# Sensors.net
KiCad netlist of a schematic drawn in Altium Designer
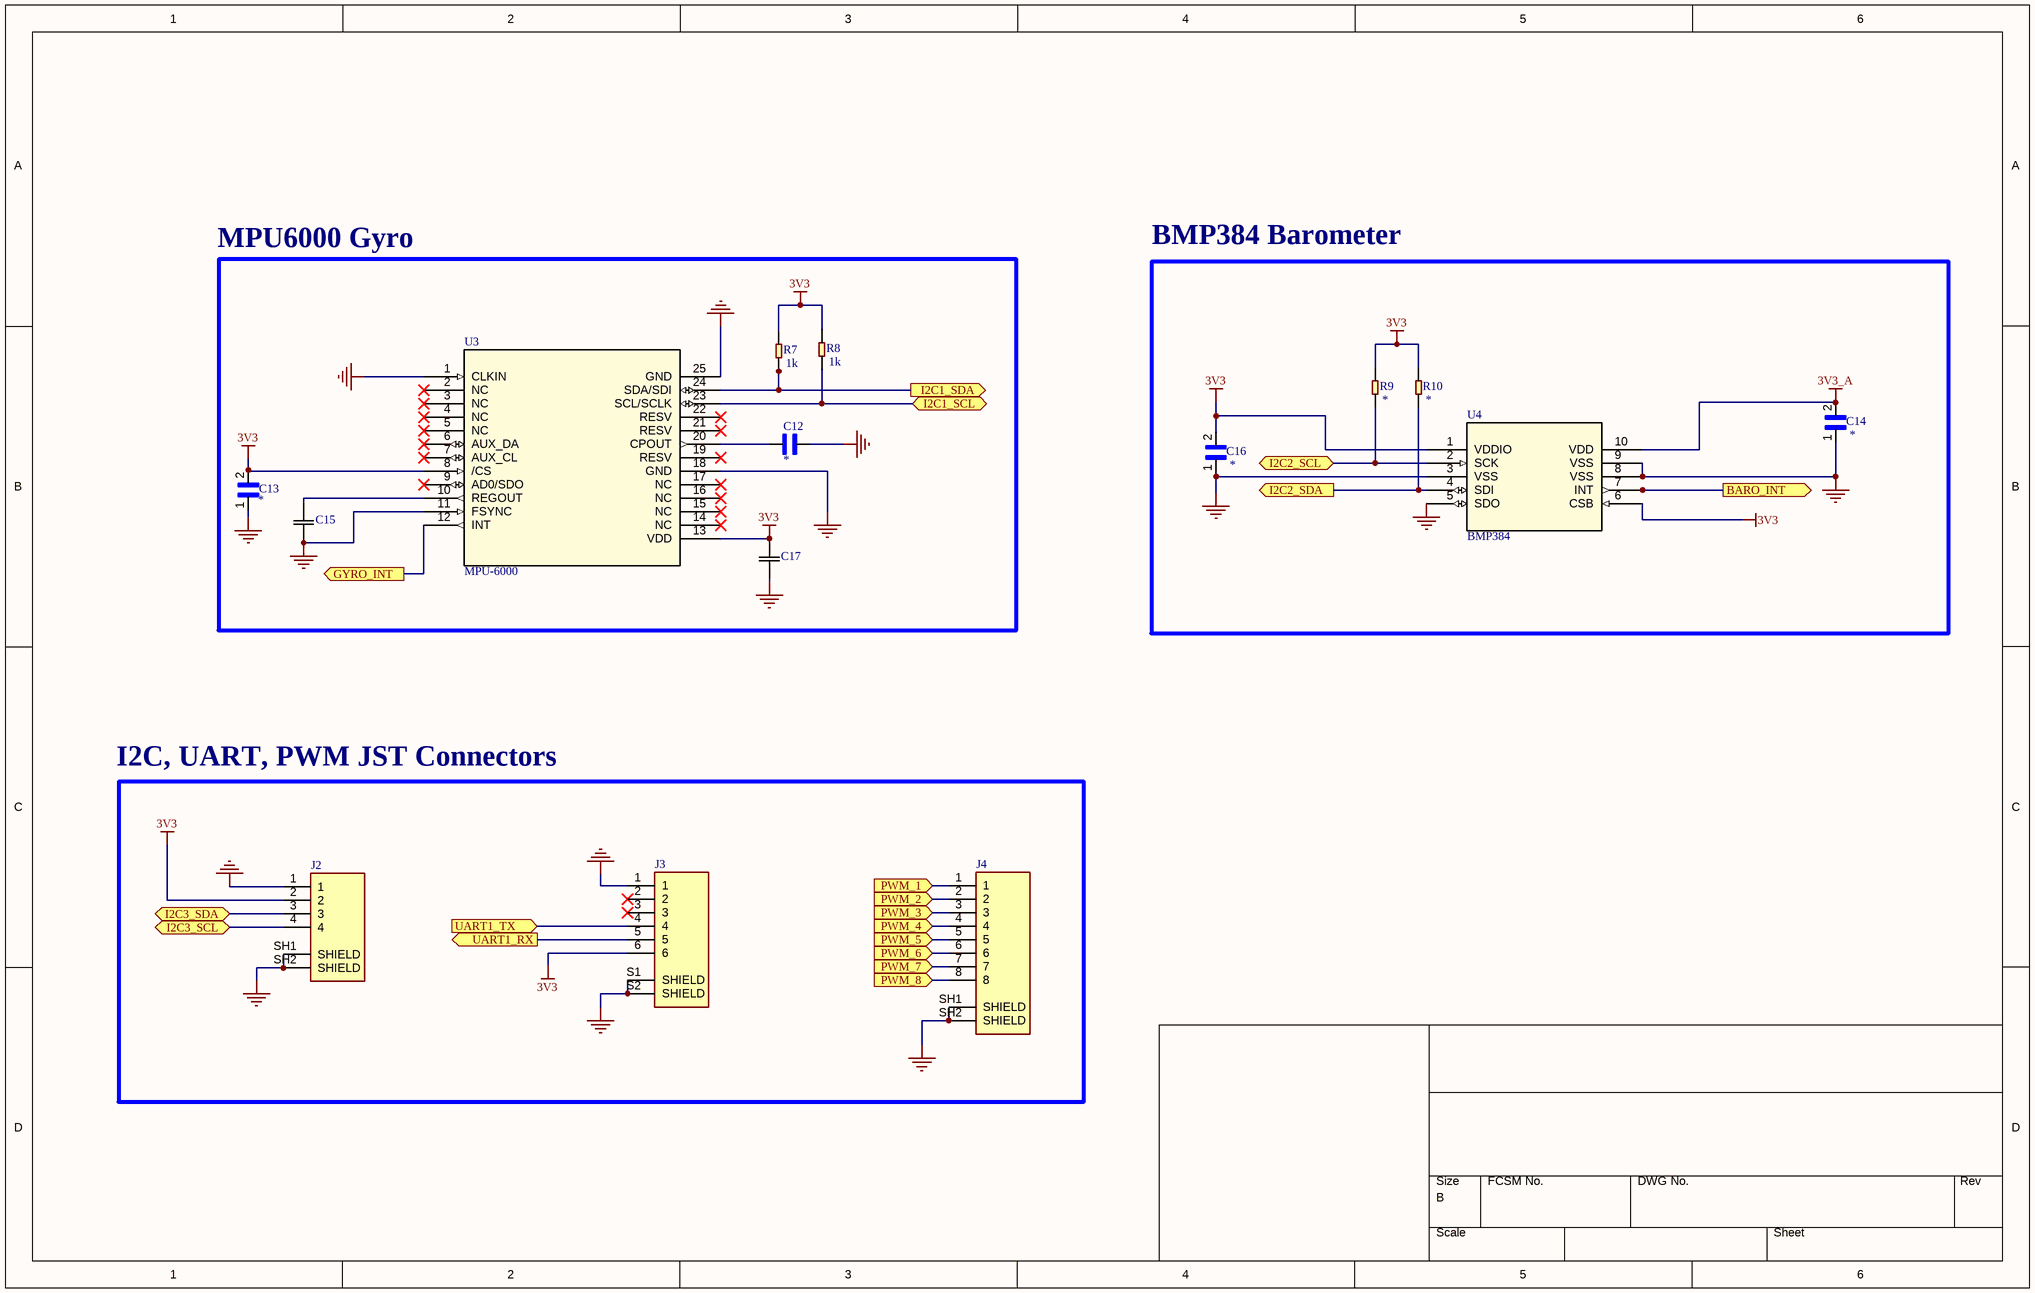
[diagram p0: Sensors.SchDoc]

(export (version "E")
  (design (tool "Eeschema 10.0.6"))
  (components
    (comp (ref "C12")
      (value "GRM155R70J222KA01D")
      (footprint "CAPC1005X55N")
      (description "Cap Ceramic 0.0022uF 6.3V X7R 10% SMD 0402 125Â°C Paper T/R")
      (fields (field (name "ALTIUM_VALUE") "*"))
      (libsource (lib "GRM155R70J222KA01D") (part "GRM155R70J222KA01D"))
    )
    (comp (ref "C13")
      (value "GRM033R71A103KA01D")
      (footprint "CAPC0603X33N")
      (description "SMD Capacitor X7R(EIA) with Capacitance: 10000pF Tol. 10%. Rated Voltage: 10Vdc")
      (fields (field (name "ALTIUM_VALUE") "*") (field (name "MF") "Murata"))
      (libsource (lib "GRM033R71A103KA01D") (part "GRM033R71A103KA01D"))
    )
    (comp (ref "C14")
      (value "GRM033R61A104KE15D")
      (footprint "CAPC0603X33N")
      (description "SMD capacitor X5R(EIA) with capacitance 0.10uF Tol.10%. Rated voltage 10Vdc 85C")
      (fields (field (name "MF") "Murata Electronics") (field (name "ALTIUM_VALUE") "*"))
      (libsource (lib "GRM033R61A104KE15D") (part "GRM033R61A104KE15D"))
    )
    (comp (ref "C15")
      (value "CC0201MRX5R6BB105")
      (footprint "CAP_CC0201_YAG")
      (description "No Description Available")
      (libsource (lib "CC0201MRX5R6BB105") (part "CC0201MRX5R6BB105"))
    )
    (comp (ref "C16")
      (value "GRM033R61A104KE15D")
      (footprint "CAPC0603X33N")
      (description "SMD capacitor X5R(EIA) with capacitance 0.10uF Tol.10%. Rated voltage 10Vdc 85C")
      (fields (field (name "MF") "Murata Electronics") (field (name "ALTIUM_VALUE") "*"))
      (libsource (lib "GRM033R61A104KE15D") (part "GRM033R61A104KE15D"))
    )
    (comp (ref "C17")
      (value "CC0201MRX5R6BB105")
      (footprint "CAP_CC0201_YAG")
      (description "No Description Available")
      (libsource (lib "CC0201MRX5R6BB105") (part "CC0201MRX5R6BB105"))
    )
    (comp (ref "J2")
      (value "SM04B-GHS-TB(LF)(SN)-")
      (footprint "JST_SM04B-GHS-TB(LF)(SN)-")
      (description "Connector Header Surface Mount, Right Angle 4 position 0.049 _1.25mm_")
      (fields (field (name "MP") "SM04B-GHS-TB_LF__SN_-") (field (name "MF") "JST Sales"))
      (libsource (lib "SM04B-GHS-TB_LF__SN_-") (part "SM04B-GHS-TB(LF)(SN)-"))
    )
    (comp (ref "J3")
      (value "SM06B-GHS-TB(LF)(SN)")
      (footprint "JST_SM06B-GHS-TB(LF)(SN)")
      (fields (field (name "MP") "SM06B-GHS-TB_LF__SN_") (field (name "MF") "JST Sales"))
      (libsource (lib "SM06B-GHS-TB_LF__SN_") (part "SM06B-GHS-TB(LF)(SN)"))
    )
    (comp (ref "J4")
      (value "SM08B-GHS-TB(LF)(SN)")
      (footprint "JST_SM08B-GHS-TB(LF)(SN)")
      (description "Connector Header Surface Mount, Right Angle 8 position 0.049 _1.25mm_")
      (fields (field (name "MF") "JST Sales") (field (name "DIGI-KEY_PART_NUMBER") "455-1570-1-ND"))
      (libsource (lib "SM08B-GHS-TB_LF__SN_") (part "SM08B-GHS-TB(LF)(SN)"))
    )
    (comp (ref "R7")
      (value "1k")
      (footprint "R0402")
      (description "1 kOhms Â±5% 0.063W, 1/16W Chip Resistor 0402 (1005 Metric) Moisture Resistant Thick Film")
      (fields (field (name "MP") "RC0402JR-071KL") (field (name "DIGI-KEY_PART_NUMBER") "311-1.0KJRTR-ND"))
      (libsource (lib "SMD-RES-1K-5_-1_16W_0402_") (part "SMD-RES-1K-5%-1/16W(0402)"))
    )
    (comp (ref "R8")
      (value "1k")
      (footprint "R0402")
      (description "1 kOhms Â±5% 0.063W, 1/16W Chip Resistor 0402 (1005 Metric) Moisture Resistant Thick Film")
      (fields (field (name "MP") "RC0402JR-071KL") (field (name "DIGI-KEY_PART_NUMBER") "311-1.0KJRTR-ND"))
      (libsource (lib "SMD-RES-1K-5_-1_16W_0402_") (part "SMD-RES-1K-5%-1/16W(0402)"))
    )
    (comp (ref "R9")
      (value "SMD-RES-1K-5%-1/16W(0402)")
      (footprint "R0402")
      (description "1 kOhms Â±5% 0.063W, 1/16W Chip Resistor 0402 (1005 Metric) Moisture Resistant Thick Film")
      (fields
        (field (name "ALTIUM_VALUE") "*")
        (field (name "MP") "RC0402JR-071KL")
        (field (name "DIGI-KEY_PART_NUMBER") "311-1.0KJRTR-ND")
      )
      (libsource (lib "SMD-RES-1K-5_-1_16W_0402_") (part "SMD-RES-1K-5%-1/16W(0402)"))
    )
    (comp (ref "R10")
      (value "SMD-RES-1K-5%-1/16W(0402)")
      (footprint "R0402")
      (description "1 kOhms Â±5% 0.063W, 1/16W Chip Resistor 0402 (1005 Metric) Moisture Resistant Thick Film")
      (fields
        (field (name "ALTIUM_VALUE") "*")
        (field (name "MP") "RC0402JR-071KL")
        (field (name "DIGI-KEY_PART_NUMBER") "311-1.0KJRTR-ND")
      )
      (libsource (lib "SMD-RES-1K-5_-1_16W_0402_") (part "SMD-RES-1K-5%-1/16W(0402)"))
    )
    (comp (ref "U3")
      (value "MPU-6000")
      (footprint "QFN24_4X4X0P9_IVS")
      (description "No Description Available")
      (libsource (lib "MPU-6000") (part "MPU-6000"))
    )
    (comp (ref "U4")
      (value "BMP384")
      (footprint "LGA10_2.0X2.0X0.95_BOS")
      (description "No Description Available")
      (libsource (lib "BMP384") (part "BMP384"))
    )
  )
  (nets
    (net (code "1") (name "/BARO_INT") (class "Default")
      (node (ref "U4") (pin "7") (pinfunction "INT_7") (pintype "output"))
    )
    (net (code "2") (name "/GYRO_INT") (class "Default")
      (node (ref "U3") (pin "12") (pinfunction "INT_12") (pintype "output"))
    )
    (net (code "3") (name "/I2C1_SCL") (class "Default")
      (node (ref "R8") (pin "1") (pinfunction "1_1") (pintype "passive"))
      (node (ref "U3") (pin "23") (pinfunction "SCL/SCLK_23") (pintype "bidirectional"))
    )
    (net (code "4") (name "/I2C1_SDA") (class "Default")
      (node (ref "R7") (pin "1") (pinfunction "1_1") (pintype "passive"))
      (node (ref "U3") (pin "24") (pinfunction "SDA/SDI_24") (pintype "bidirectional"))
    )
    (net (code "5") (name "/I2C2_SCL") (class "Default")
      (node (ref "R9") (pin "1") (pinfunction "1_1") (pintype "passive"))
      (node (ref "U4") (pin "2") (pinfunction "SCK_2") (pintype "input"))
    )
    (net (code "6") (name "/I2C2_SDA") (class "Default")
      (node (ref "R10") (pin "1") (pinfunction "1_1") (pintype "passive"))
      (node (ref "U4") (pin "4") (pinfunction "SDI_4") (pintype "bidirectional"))
    )
    (net (code "7") (name "/I2C3_SCL") (class "Default")
      (node (ref "J2") (pin "4") (pinfunction "4_4") (pintype "passive"))
    )
    (net (code "8") (name "/I2C3_SDA") (class "Default")
      (node (ref "J2") (pin "3") (pinfunction "3_3") (pintype "passive"))
    )
    (net (code "9") (name "/PWM_1") (class "Default")
      (node (ref "J4") (pin "1") (pinfunction "1_1") (pintype "passive"))
    )
    (net (code "10") (name "/PWM_2") (class "Default")
      (node (ref "J4") (pin "2") (pinfunction "2_2") (pintype "passive"))
    )
    (net (code "11") (name "/PWM_3") (class "Default")
      (node (ref "J4") (pin "3") (pinfunction "3_3") (pintype "passive"))
    )
    (net (code "12") (name "/PWM_4") (class "Default")
      (node (ref "J4") (pin "4") (pinfunction "4_4") (pintype "passive"))
    )
    (net (code "13") (name "/PWM_5") (class "Default")
      (node (ref "J4") (pin "5") (pinfunction "5_5") (pintype "passive"))
    )
    (net (code "14") (name "/PWM_6") (class "Default")
      (node (ref "J4") (pin "6") (pinfunction "6_6") (pintype "passive"))
    )
    (net (code "15") (name "/PWM_7") (class "Default")
      (node (ref "J4") (pin "7") (pinfunction "7_7") (pintype "passive"))
    )
    (net (code "16") (name "/PWM_8") (class "Default")
      (node (ref "J4") (pin "8") (pinfunction "8_8") (pintype "passive"))
    )
    (net (code "17") (name "/UART1_RX") (class "Default")
      (node (ref "J3") (pin "5") (pinfunction "5_5") (pintype "passive"))
    )
    (net (code "18") (name "/UART1_TX") (class "Default")
      (node (ref "J3") (pin "4") (pinfunction "4_4") (pintype "passive"))
    )
    (net (code "19") (name "3V3") (class "Default")
      (node (ref "C13") (pin "2") (pinfunction "2_2") (pintype "passive"))
      (node (ref "C16") (pin "2") (pinfunction "2_2") (pintype "passive"))
      (node (ref "C17") (pin "2") (pinfunction "2_2") (pintype "passive"))
      (node (ref "J2") (pin "2") (pinfunction "2_2") (pintype "passive"))
      (node (ref "J3") (pin "6") (pinfunction "6_6") (pintype "passive"))
      (node (ref "R10") (pin "2") (pinfunction "2_2") (pintype "passive"))
      (node (ref "R7") (pin "2") (pinfunction "2_2") (pintype "passive"))
      (node (ref "R8") (pin "2") (pinfunction "2_2") (pintype "passive"))
      (node (ref "R9") (pin "2") (pinfunction "2_2") (pintype "passive"))
      (node (ref "U3") (pin "13") (pinfunction "VDD_13") (pintype "power_in"))
      (node (ref "U3") (pin "8") (pinfunction "/CS_8") (pintype "input"))
      (node (ref "U4") (pin "1") (pinfunction "VDDIO_1") (pintype "power_in"))
      (node (ref "U4") (pin "6") (pinfunction "CSB_6") (pintype "input"))
    )
    (net (code "20") (name "3V3_A") (class "Default")
      (node (ref "C14") (pin "2") (pinfunction "2_2") (pintype "passive"))
      (node (ref "U4") (pin "10") (pinfunction "VDD_10") (pintype "power_in"))
    )
    (net (code "21") (name "GND") (class "Default")
      (node (ref "C12") (pin "1") (pinfunction "1_1") (pintype "passive"))
      (node (ref "C13") (pin "1") (pinfunction "1_1") (pintype "passive"))
      (node (ref "C14") (pin "1") (pinfunction "1_1") (pintype "passive"))
      (node (ref "C15") (pin "1") (pinfunction "1_1") (pintype "passive"))
      (node (ref "C16") (pin "1") (pinfunction "1_1") (pintype "passive"))
      (node (ref "C17") (pin "1") (pinfunction "1_1") (pintype "passive"))
      (node (ref "J2") (pin "1") (pinfunction "1_1") (pintype "passive"))
      (node (ref "J2") (pin "SH1") (pinfunction "SHIELD_SH1") (pintype "power_in"))
      (node (ref "J2") (pin "SH2") (pinfunction "SHIELD_SH2") (pintype "power_in"))
      (node (ref "J3") (pin "1") (pinfunction "1_1") (pintype "passive"))
      (node (ref "J3") (pin "S1") (pinfunction "SHIELD_S1") (pintype "passive"))
      (node (ref "J3") (pin "S2") (pinfunction "SHIELD_S2") (pintype "passive"))
      (node (ref "J4") (pin "SH1") (pinfunction "SHIELD_SH1") (pintype "passive"))
      (node (ref "J4") (pin "SH2") (pinfunction "SHIELD_SH2") (pintype "passive"))
      (node (ref "U3") (pin "1") (pinfunction "CLKIN_1") (pintype "input"))
      (node (ref "U3") (pin "11") (pinfunction "FSYNC_11") (pintype "input"))
      (node (ref "U3") (pin "18") (pinfunction "GND_18") (pintype "power_in"))
      (node (ref "U3") (pin "25") (pinfunction "GND_25") (pintype "power_in"))
      (node (ref "U4") (pin "3") (pinfunction "VSS_3") (pintype "power_in"))
      (node (ref "U4") (pin "5") (pinfunction "SDO_5") (pintype "bidirectional"))
      (node (ref "U4") (pin "8") (pinfunction "VSS_8") (pintype "power_in"))
      (node (ref "U4") (pin "9") (pinfunction "VSS_9") (pintype "power_in"))
    )
    (net (code "22") (name "Net-(U3-CPOUT)") (class "Default")
      (node (ref "C12") (pin "2") (pinfunction "2_2") (pintype "passive"))
      (node (ref "U3") (pin "20") (pinfunction "CPOUT_20") (pintype "output"))
    )
    (net (code "23") (name "Net-(U3-REGOUT)") (class "Default")
      (node (ref "C15") (pin "2") (pinfunction "2_2") (pintype "passive"))
      (node (ref "U3") (pin "10") (pinfunction "REGOUT_10") (pintype "output"))
    )
    (net (code "24") (name "unconnected-(J3-Pad2)") (class "Default")
      (node (ref "J3") (pin "2") (pinfunction "2_2") (pintype "passive+no_connect"))
    )
    (net (code "25") (name "unconnected-(J3-Pad3)") (class "Default")
      (node (ref "J3") (pin "3") (pinfunction "3_3") (pintype "passive+no_connect"))
    )
    (net (code "26") (name "unconnected-(U3-AD0{slash}SDO-Pad9)") (class "Default")
      (node (ref "U3") (pin "9") (pinfunction "AD0/SDO_9") (pintype "bidirectional+no_connect"))
    )
    (net (code "27") (name "unconnected-(U3-AUX_CL-Pad7)") (class "Default")
      (node (ref "U3") (pin "7") (pinfunction "AUX_CL_7") (pintype "bidirectional+no_connect"))
    )
    (net (code "28") (name "unconnected-(U3-AUX_DA-Pad6)") (class "Default")
      (node (ref "U3") (pin "6") (pinfunction "AUX_DA_6") (pintype "bidirectional+no_connect"))
    )
    (net (code "29") (name "unconnected-(U3-NC-Pad2)") (class "Default")
      (node (ref "U3") (pin "2") (pinfunction "NC_2") (pintype "passive+no_connect"))
    )
    (net (code "30") (name "unconnected-(U3-NC-Pad3)") (class "Default")
      (node (ref "U3") (pin "3") (pinfunction "NC_3") (pintype "passive+no_connect"))
    )
    (net (code "31") (name "unconnected-(U3-NC-Pad4)") (class "Default")
      (node (ref "U3") (pin "4") (pinfunction "NC_4") (pintype "passive+no_connect"))
    )
    (net (code "32") (name "unconnected-(U3-NC-Pad5)") (class "Default")
      (node (ref "U3") (pin "5") (pinfunction "NC_5") (pintype "passive+no_connect"))
    )
    (net (code "33") (name "unconnected-(U3-NC-Pad14)") (class "Default")
      (node (ref "U3") (pin "14") (pinfunction "NC_14") (pintype "passive+no_connect"))
    )
    (net (code "34") (name "unconnected-(U3-NC-Pad15)") (class "Default")
      (node (ref "U3") (pin "15") (pinfunction "NC_15") (pintype "passive+no_connect"))
    )
    (net (code "35") (name "unconnected-(U3-NC-Pad16)") (class "Default")
      (node (ref "U3") (pin "16") (pinfunction "NC_16") (pintype "passive+no_connect"))
    )
    (net (code "36") (name "unconnected-(U3-NC-Pad17)") (class "Default")
      (node (ref "U3") (pin "17") (pinfunction "NC_17") (pintype "passive+no_connect"))
    )
    (net (code "37") (name "unconnected-(U3-RESV-Pad19)") (class "Default")
      (node (ref "U3") (pin "19") (pinfunction "RESV_19") (pintype "passive+no_connect"))
    )
    (net (code "38") (name "unconnected-(U3-RESV-Pad21)") (class "Default")
      (node (ref "U3") (pin "21") (pinfunction "RESV_21") (pintype "passive+no_connect"))
    )
    (net (code "39") (name "unconnected-(U3-RESV-Pad22)") (class "Default")
      (node (ref "U3") (pin "22") (pinfunction "RESV_22") (pintype "passive+no_connect"))
    )
  )
)
